# driver_board_v3_shift_regs.net
KiCad netlist of a schematic drawn in EAGLE
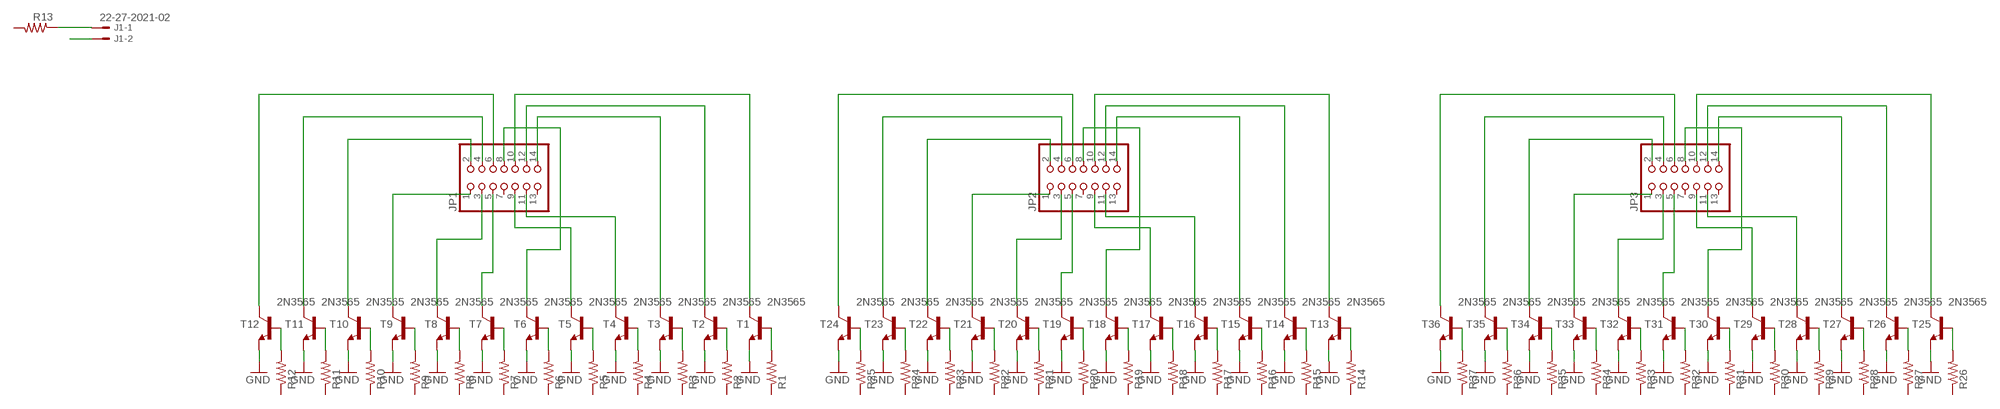
[diagram p0: schematic, sheet 1, part 1 of 2]
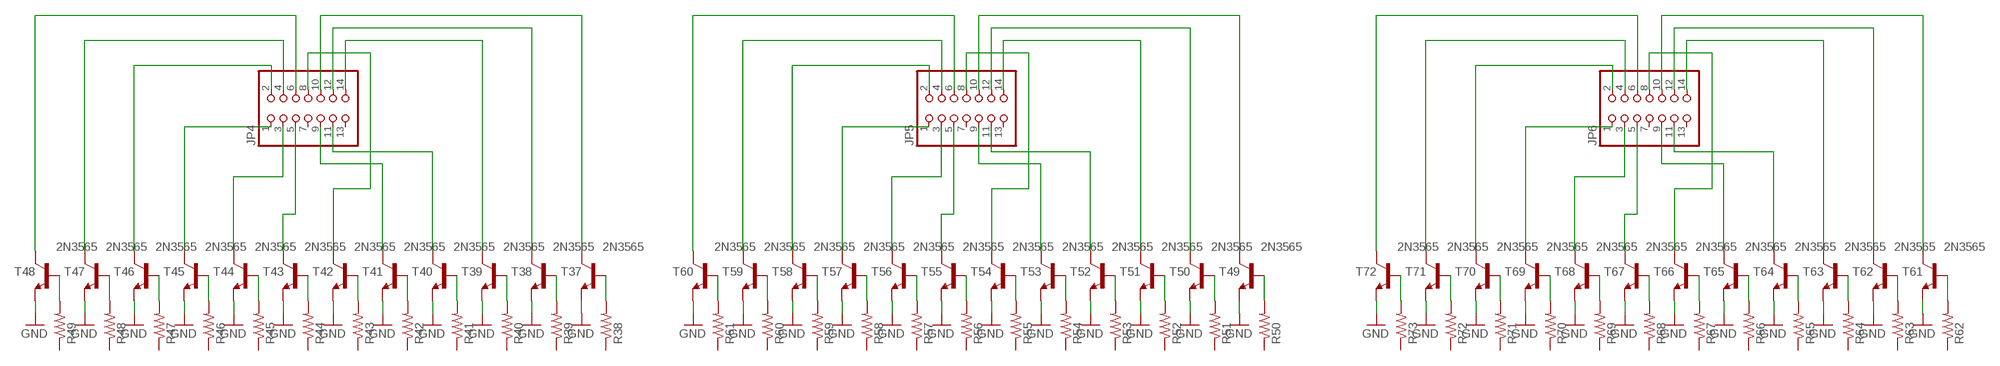
[diagram p1: schematic, sheet 1, part 2 of 2]

(export (version "E")
  (design (tool "Eeschema 10.0.6"))
  (components
    (comp (ref "J1")
      (value "22-27-2021-02")
      (footprint "eagle-import:6410-02")
      (libsource (lib "eagle-import") (part "22-?-0227-2021"))
    )
    (comp (ref "JP1")
      (value "PINHD-2X7")
      (footprint "eagle-import:2X07")
      (libsource (lib "eagle-import") (part "PINHD-2X7"))
    )
    (comp (ref "JP2")
      (value "PINHD-2X7")
      (footprint "eagle-import:2X07")
      (libsource (lib "eagle-import") (part "PINHD-2X7"))
    )
    (comp (ref "JP3")
      (value "PINHD-2X7")
      (footprint "eagle-import:2X07")
      (libsource (lib "eagle-import") (part "PINHD-2X7"))
    )
    (comp (ref "JP4")
      (value "PINHD-2X7")
      (footprint "eagle-import:2X07")
      (libsource (lib "eagle-import") (part "PINHD-2X7"))
    )
    (comp (ref "JP5")
      (value "PINHD-2X7")
      (footprint "eagle-import:2X07")
      (libsource (lib "eagle-import") (part "PINHD-2X7"))
    )
    (comp (ref "JP6")
      (value "PINHD-2X7")
      (footprint "eagle-import:2X07")
      (libsource (lib "eagle-import") (part "PINHD-2X7"))
    )
    (comp (ref "R1")
      (value "R-US_0204/7")
      (footprint "eagle-import:0204_7")
      (libsource (lib "eagle-import") (part "R-US_0204/7"))
    )
    (comp (ref "R2")
      (value "R-US_0204/7")
      (footprint "eagle-import:0204_7")
      (libsource (lib "eagle-import") (part "R-US_0204/7"))
    )
    (comp (ref "R3")
      (value "R-US_0204/7")
      (footprint "eagle-import:0204_7")
      (libsource (lib "eagle-import") (part "R-US_0204/7"))
    )
    (comp (ref "R4")
      (value "R-US_0204/7")
      (footprint "eagle-import:0204_7")
      (libsource (lib "eagle-import") (part "R-US_0204/7"))
    )
    (comp (ref "R5")
      (value "R-US_0204/7")
      (footprint "eagle-import:0204_7")
      (libsource (lib "eagle-import") (part "R-US_0204/7"))
    )
    (comp (ref "R6")
      (value "R-US_0204/7")
      (footprint "eagle-import:0204_7")
      (libsource (lib "eagle-import") (part "R-US_0204/7"))
    )
    (comp (ref "R7")
      (value "R-US_0204/7")
      (footprint "eagle-import:0204_7")
      (libsource (lib "eagle-import") (part "R-US_0204/7"))
    )
    (comp (ref "R8")
      (value "R-US_0204/7")
      (footprint "eagle-import:0204_7")
      (libsource (lib "eagle-import") (part "R-US_0204/7"))
    )
    (comp (ref "R9")
      (value "R-US_0204/7")
      (footprint "eagle-import:0204_7")
      (libsource (lib "eagle-import") (part "R-US_0204/7"))
    )
    (comp (ref "R10")
      (value "R-US_0204/7")
      (footprint "eagle-import:0204_7")
      (libsource (lib "eagle-import") (part "R-US_0204/7"))
    )
    (comp (ref "R11")
      (value "R-US_0204/7")
      (footprint "eagle-import:0204_7")
      (libsource (lib "eagle-import") (part "R-US_0204/7"))
    )
    (comp (ref "R12")
      (value "R-US_0204/7")
      (footprint "eagle-import:0204_7")
      (libsource (lib "eagle-import") (part "R-US_0204/7"))
    )
    (comp (ref "R13")
      (value "R-US_0204/7")
      (footprint "eagle-import:0204_7")
      (libsource (lib "eagle-import") (part "R-US_0204/7"))
    )
    (comp (ref "R14")
      (value "R-US_0204/7")
      (footprint "eagle-import:0204_7")
      (libsource (lib "eagle-import") (part "R-US_0204/7"))
    )
    (comp (ref "R15")
      (value "R-US_0204/7")
      (footprint "eagle-import:0204_7")
      (libsource (lib "eagle-import") (part "R-US_0204/7"))
    )
    (comp (ref "R16")
      (value "R-US_0204/7")
      (footprint "eagle-import:0204_7")
      (libsource (lib "eagle-import") (part "R-US_0204/7"))
    )
    (comp (ref "R17")
      (value "R-US_0204/7")
      (footprint "eagle-import:0204_7")
      (libsource (lib "eagle-import") (part "R-US_0204/7"))
    )
    (comp (ref "R18")
      (value "R-US_0204/7")
      (footprint "eagle-import:0204_7")
      (libsource (lib "eagle-import") (part "R-US_0204/7"))
    )
    (comp (ref "R19")
      (value "R-US_0204/7")
      (footprint "eagle-import:0204_7")
      (libsource (lib "eagle-import") (part "R-US_0204/7"))
    )
    (comp (ref "R20")
      (value "R-US_0204/7")
      (footprint "eagle-import:0204_7")
      (libsource (lib "eagle-import") (part "R-US_0204/7"))
    )
    (comp (ref "R21")
      (value "R-US_0204/7")
      (footprint "eagle-import:0204_7")
      (libsource (lib "eagle-import") (part "R-US_0204/7"))
    )
    (comp (ref "R22")
      (value "R-US_0204/7")
      (footprint "eagle-import:0204_7")
      (libsource (lib "eagle-import") (part "R-US_0204/7"))
    )
    (comp (ref "R23")
      (value "R-US_0204/7")
      (footprint "eagle-import:0204_7")
      (libsource (lib "eagle-import") (part "R-US_0204/7"))
    )
    (comp (ref "R24")
      (value "R-US_0204/7")
      (footprint "eagle-import:0204_7")
      (libsource (lib "eagle-import") (part "R-US_0204/7"))
    )
    (comp (ref "R25")
      (value "R-US_0204/7")
      (footprint "eagle-import:0204_7")
      (libsource (lib "eagle-import") (part "R-US_0204/7"))
    )
    (comp (ref "R26")
      (value "R-US_0204/7")
      (footprint "eagle-import:0204_7")
      (libsource (lib "eagle-import") (part "R-US_0204/7"))
    )
    (comp (ref "R27")
      (value "R-US_0204/7")
      (footprint "eagle-import:0204_7")
      (libsource (lib "eagle-import") (part "R-US_0204/7"))
    )
    (comp (ref "R28")
      (value "R-US_0204/7")
      (footprint "eagle-import:0204_7")
      (libsource (lib "eagle-import") (part "R-US_0204/7"))
    )
    (comp (ref "R29")
      (value "R-US_0204/7")
      (footprint "eagle-import:0204_7")
      (libsource (lib "eagle-import") (part "R-US_0204/7"))
    )
    (comp (ref "R30")
      (value "R-US_0204/7")
      (footprint "eagle-import:0204_7")
      (libsource (lib "eagle-import") (part "R-US_0204/7"))
    )
    (comp (ref "R31")
      (value "R-US_0204/7")
      (footprint "eagle-import:0204_7")
      (libsource (lib "eagle-import") (part "R-US_0204/7"))
    )
    (comp (ref "R32")
      (value "R-US_0204/7")
      (footprint "eagle-import:0204_7")
      (libsource (lib "eagle-import") (part "R-US_0204/7"))
    )
    (comp (ref "R33")
      (value "R-US_0204/7")
      (footprint "eagle-import:0204_7")
      (libsource (lib "eagle-import") (part "R-US_0204/7"))
    )
    (comp (ref "R34")
      (value "R-US_0204/7")
      (footprint "eagle-import:0204_7")
      (libsource (lib "eagle-import") (part "R-US_0204/7"))
    )
    (comp (ref "R35")
      (value "R-US_0204/7")
      (footprint "eagle-import:0204_7")
      (libsource (lib "eagle-import") (part "R-US_0204/7"))
    )
    (comp (ref "R36")
      (value "R-US_0204/7")
      (footprint "eagle-import:0204_7")
      (libsource (lib "eagle-import") (part "R-US_0204/7"))
    )
    (comp (ref "R37")
      (value "R-US_0204/7")
      (footprint "eagle-import:0204_7")
      (libsource (lib "eagle-import") (part "R-US_0204/7"))
    )
    (comp (ref "R38")
      (value "R-US_0204/7")
      (footprint "eagle-import:0204_7")
      (libsource (lib "eagle-import") (part "R-US_0204/7"))
    )
    (comp (ref "R39")
      (value "R-US_0204/7")
      (footprint "eagle-import:0204_7")
      (libsource (lib "eagle-import") (part "R-US_0204/7"))
    )
    (comp (ref "R40")
      (value "R-US_0204/7")
      (footprint "eagle-import:0204_7")
      (libsource (lib "eagle-import") (part "R-US_0204/7"))
    )
    (comp (ref "R41")
      (value "R-US_0204/7")
      (footprint "eagle-import:0204_7")
      (libsource (lib "eagle-import") (part "R-US_0204/7"))
    )
    (comp (ref "R42")
      (value "R-US_0204/7")
      (footprint "eagle-import:0204_7")
      (libsource (lib "eagle-import") (part "R-US_0204/7"))
    )
    (comp (ref "R43")
      (value "R-US_0204/7")
      (footprint "eagle-import:0204_7")
      (libsource (lib "eagle-import") (part "R-US_0204/7"))
    )
    (comp (ref "R44")
      (value "R-US_0204/7")
      (footprint "eagle-import:0204_7")
      (libsource (lib "eagle-import") (part "R-US_0204/7"))
    )
    (comp (ref "R45")
      (value "R-US_0204/7")
      (footprint "eagle-import:0204_7")
      (libsource (lib "eagle-import") (part "R-US_0204/7"))
    )
    (comp (ref "R46")
      (value "R-US_0204/7")
      (footprint "eagle-import:0204_7")
      (libsource (lib "eagle-import") (part "R-US_0204/7"))
    )
    (comp (ref "R47")
      (value "R-US_0204/7")
      (footprint "eagle-import:0204_7")
      (libsource (lib "eagle-import") (part "R-US_0204/7"))
    )
    (comp (ref "R48")
      (value "R-US_0204/7")
      (footprint "eagle-import:0204_7")
      (libsource (lib "eagle-import") (part "R-US_0204/7"))
    )
    (comp (ref "R49")
      (value "R-US_0204/7")
      (footprint "eagle-import:0204_7")
      (libsource (lib "eagle-import") (part "R-US_0204/7"))
    )
    (comp (ref "R50")
      (value "R-US_0204/7")
      (footprint "eagle-import:0204_7")
      (libsource (lib "eagle-import") (part "R-US_0204/7"))
    )
    (comp (ref "R51")
      (value "R-US_0204/7")
      (footprint "eagle-import:0204_7")
      (libsource (lib "eagle-import") (part "R-US_0204/7"))
    )
    (comp (ref "R52")
      (value "R-US_0204/7")
      (footprint "eagle-import:0204_7")
      (libsource (lib "eagle-import") (part "R-US_0204/7"))
    )
    (comp (ref "R53")
      (value "R-US_0204/7")
      (footprint "eagle-import:0204_7")
      (libsource (lib "eagle-import") (part "R-US_0204/7"))
    )
    (comp (ref "R54")
      (value "R-US_0204/7")
      (footprint "eagle-import:0204_7")
      (libsource (lib "eagle-import") (part "R-US_0204/7"))
    )
    (comp (ref "R55")
      (value "R-US_0204/7")
      (footprint "eagle-import:0204_7")
      (libsource (lib "eagle-import") (part "R-US_0204/7"))
    )
    (comp (ref "R56")
      (value "R-US_0204/7")
      (footprint "eagle-import:0204_7")
      (libsource (lib "eagle-import") (part "R-US_0204/7"))
    )
    (comp (ref "R57")
      (value "R-US_0204/7")
      (footprint "eagle-import:0204_7")
      (libsource (lib "eagle-import") (part "R-US_0204/7"))
    )
    (comp (ref "R58")
      (value "R-US_0204/7")
      (footprint "eagle-import:0204_7")
      (libsource (lib "eagle-import") (part "R-US_0204/7"))
    )
    (comp (ref "R59")
      (value "R-US_0204/7")
      (footprint "eagle-import:0204_7")
      (libsource (lib "eagle-import") (part "R-US_0204/7"))
    )
    (comp (ref "R60")
      (value "R-US_0204/7")
      (footprint "eagle-import:0204_7")
      (libsource (lib "eagle-import") (part "R-US_0204/7"))
    )
    (comp (ref "R61")
      (value "R-US_0204/7")
      (footprint "eagle-import:0204_7")
      (libsource (lib "eagle-import") (part "R-US_0204/7"))
    )
    (comp (ref "R62")
      (value "R-US_0204/7")
      (footprint "eagle-import:0204_7")
      (libsource (lib "eagle-import") (part "R-US_0204/7"))
    )
    (comp (ref "R63")
      (value "R-US_0204/7")
      (footprint "eagle-import:0204_7")
      (libsource (lib "eagle-import") (part "R-US_0204/7"))
    )
    (comp (ref "R64")
      (value "R-US_0204/7")
      (footprint "eagle-import:0204_7")
      (libsource (lib "eagle-import") (part "R-US_0204/7"))
    )
    (comp (ref "R65")
      (value "R-US_0204/7")
      (footprint "eagle-import:0204_7")
      (libsource (lib "eagle-import") (part "R-US_0204/7"))
    )
    (comp (ref "R66")
      (value "R-US_0204/7")
      (footprint "eagle-import:0204_7")
      (libsource (lib "eagle-import") (part "R-US_0204/7"))
    )
    (comp (ref "R67")
      (value "R-US_0204/7")
      (footprint "eagle-import:0204_7")
      (libsource (lib "eagle-import") (part "R-US_0204/7"))
    )
    (comp (ref "R68")
      (value "R-US_0204/7")
      (footprint "eagle-import:0204_7")
      (libsource (lib "eagle-import") (part "R-US_0204/7"))
    )
    (comp (ref "R69")
      (value "R-US_0204/7")
      (footprint "eagle-import:0204_7")
      (libsource (lib "eagle-import") (part "R-US_0204/7"))
    )
    (comp (ref "R70")
      (value "R-US_0204/7")
      (footprint "eagle-import:0204_7")
      (libsource (lib "eagle-import") (part "R-US_0204/7"))
    )
    (comp (ref "R71")
      (value "R-US_0204/7")
      (footprint "eagle-import:0204_7")
      (libsource (lib "eagle-import") (part "R-US_0204/7"))
    )
    (comp (ref "R72")
      (value "R-US_0204/7")
      (footprint "eagle-import:0204_7")
      (libsource (lib "eagle-import") (part "R-US_0204/7"))
    )
    (comp (ref "R73")
      (value "R-US_0204/7")
      (footprint "eagle-import:0204_7")
      (libsource (lib "eagle-import") (part "R-US_0204/7"))
    )
    (comp (ref "T1")
      (value "2N3565")
      (footprint "eagle-import:TO92")
      (libsource (lib "eagle-import") (part "2N3565"))
    )
    (comp (ref "T2")
      (value "2N3565")
      (footprint "eagle-import:TO92")
      (libsource (lib "eagle-import") (part "2N3565"))
    )
    (comp (ref "T3")
      (value "2N3565")
      (footprint "eagle-import:TO92")
      (libsource (lib "eagle-import") (part "2N3565"))
    )
    (comp (ref "T4")
      (value "2N3565")
      (footprint "eagle-import:TO92")
      (libsource (lib "eagle-import") (part "2N3565"))
    )
    (comp (ref "T5")
      (value "2N3565")
      (footprint "eagle-import:TO92")
      (libsource (lib "eagle-import") (part "2N3565"))
    )
    (comp (ref "T6")
      (value "2N3565")
      (footprint "eagle-import:TO92")
      (libsource (lib "eagle-import") (part "2N3565"))
    )
    (comp (ref "T7")
      (value "2N3565")
      (footprint "eagle-import:TO92")
      (libsource (lib "eagle-import") (part "2N3565"))
    )
    (comp (ref "T8")
      (value "2N3565")
      (footprint "eagle-import:TO92")
      (libsource (lib "eagle-import") (part "2N3565"))
    )
    (comp (ref "T9")
      (value "2N3565")
      (footprint "eagle-import:TO92")
      (libsource (lib "eagle-import") (part "2N3565"))
    )
    (comp (ref "T10")
      (value "2N3565")
      (footprint "eagle-import:TO92")
      (libsource (lib "eagle-import") (part "2N3565"))
    )
    (comp (ref "T11")
      (value "2N3565")
      (footprint "eagle-import:TO92")
      (libsource (lib "eagle-import") (part "2N3565"))
    )
    (comp (ref "T12")
      (value "2N3565")
      (footprint "eagle-import:TO92")
      (libsource (lib "eagle-import") (part "2N3565"))
    )
    (comp (ref "T13")
      (value "2N3565")
      (footprint "eagle-import:TO92")
      (libsource (lib "eagle-import") (part "2N3565"))
    )
    (comp (ref "T14")
      (value "2N3565")
      (footprint "eagle-import:TO92")
      (libsource (lib "eagle-import") (part "2N3565"))
    )
    (comp (ref "T15")
      (value "2N3565")
      (footprint "eagle-import:TO92")
      (libsource (lib "eagle-import") (part "2N3565"))
    )
    (comp (ref "T16")
      (value "2N3565")
      (footprint "eagle-import:TO92")
      (libsource (lib "eagle-import") (part "2N3565"))
    )
    (comp (ref "T17")
      (value "2N3565")
      (footprint "eagle-import:TO92")
      (libsource (lib "eagle-import") (part "2N3565"))
    )
    (comp (ref "T18")
      (value "2N3565")
      (footprint "eagle-import:TO92")
      (libsource (lib "eagle-import") (part "2N3565"))
    )
    (comp (ref "T19")
      (value "2N3565")
      (footprint "eagle-import:TO92")
      (libsource (lib "eagle-import") (part "2N3565"))
    )
    (comp (ref "T20")
      (value "2N3565")
      (footprint "eagle-import:TO92")
      (libsource (lib "eagle-import") (part "2N3565"))
    )
    (comp (ref "T21")
      (value "2N3565")
      (footprint "eagle-import:TO92")
      (libsource (lib "eagle-import") (part "2N3565"))
    )
    (comp (ref "T22")
      (value "2N3565")
      (footprint "eagle-import:TO92")
      (libsource (lib "eagle-import") (part "2N3565"))
    )
    (comp (ref "T23")
      (value "2N3565")
      (footprint "eagle-import:TO92")
      (libsource (lib "eagle-import") (part "2N3565"))
    )
    (comp (ref "T24")
      (value "2N3565")
      (footprint "eagle-import:TO92")
      (libsource (lib "eagle-import") (part "2N3565"))
    )
    (comp (ref "T25")
      (value "2N3565")
      (footprint "eagle-import:TO92")
      (libsource (lib "eagle-import") (part "2N3565"))
    )
    (comp (ref "T26")
      (value "2N3565")
      (footprint "eagle-import:TO92")
      (libsource (lib "eagle-import") (part "2N3565"))
    )
    (comp (ref "T27")
      (value "2N3565")
      (footprint "eagle-import:TO92")
      (libsource (lib "eagle-import") (part "2N3565"))
    )
    (comp (ref "T28")
      (value "2N3565")
      (footprint "eagle-import:TO92")
      (libsource (lib "eagle-import") (part "2N3565"))
    )
    (comp (ref "T29")
      (value "2N3565")
      (footprint "eagle-import:TO92")
      (libsource (lib "eagle-import") (part "2N3565"))
    )
    (comp (ref "T30")
      (value "2N3565")
      (footprint "eagle-import:TO92")
      (libsource (lib "eagle-import") (part "2N3565"))
    )
    (comp (ref "T31")
      (value "2N3565")
      (footprint "eagle-import:TO92")
      (libsource (lib "eagle-import") (part "2N3565"))
    )
    (comp (ref "T32")
      (value "2N3565")
      (footprint "eagle-import:TO92")
      (libsource (lib "eagle-import") (part "2N3565"))
    )
    (comp (ref "T33")
      (value "2N3565")
      (footprint "eagle-import:TO92")
      (libsource (lib "eagle-import") (part "2N3565"))
    )
    (comp (ref "T34")
      (value "2N3565")
      (footprint "eagle-import:TO92")
      (libsource (lib "eagle-import") (part "2N3565"))
    )
    (comp (ref "T35")
      (value "2N3565")
      (footprint "eagle-import:TO92")
      (libsource (lib "eagle-import") (part "2N3565"))
    )
    (comp (ref "T36")
      (value "2N3565")
      (footprint "eagle-import:TO92")
      (libsource (lib "eagle-import") (part "2N3565"))
    )
    (comp (ref "T37")
      (value "2N3565")
      (footprint "eagle-import:TO92")
      (libsource (lib "eagle-import") (part "2N3565"))
    )
    (comp (ref "T38")
      (value "2N3565")
      (footprint "eagle-import:TO92")
      (libsource (lib "eagle-import") (part "2N3565"))
    )
    (comp (ref "T39")
      (value "2N3565")
      (footprint "eagle-import:TO92")
      (libsource (lib "eagle-import") (part "2N3565"))
    )
    (comp (ref "T40")
      (value "2N3565")
      (footprint "eagle-import:TO92")
      (libsource (lib "eagle-import") (part "2N3565"))
    )
    (comp (ref "T41")
      (value "2N3565")
      (footprint "eagle-import:TO92")
      (libsource (lib "eagle-import") (part "2N3565"))
    )
    (comp (ref "T42")
      (value "2N3565")
      (footprint "eagle-import:TO92")
      (libsource (lib "eagle-import") (part "2N3565"))
    )
    (comp (ref "T43")
      (value "2N3565")
      (footprint "eagle-import:TO92")
      (libsource (lib "eagle-import") (part "2N3565"))
    )
    (comp (ref "T44")
      (value "2N3565")
      (footprint "eagle-import:TO92")
      (libsource (lib "eagle-import") (part "2N3565"))
    )
    (comp (ref "T45")
      (value "2N3565")
      (footprint "eagle-import:TO92")
      (libsource (lib "eagle-import") (part "2N3565"))
    )
    (comp (ref "T46")
      (value "2N3565")
      (footprint "eagle-import:TO92")
      (libsource (lib "eagle-import") (part "2N3565"))
    )
    (comp (ref "T47")
      (value "2N3565")
      (footprint "eagle-import:TO92")
      (libsource (lib "eagle-import") (part "2N3565"))
    )
    (comp (ref "T48")
      (value "2N3565")
      (footprint "eagle-import:TO92")
      (libsource (lib "eagle-import") (part "2N3565"))
    )
    (comp (ref "T49")
      (value "2N3565")
      (footprint "eagle-import:TO92")
      (libsource (lib "eagle-import") (part "2N3565"))
    )
    (comp (ref "T50")
      (value "2N3565")
      (footprint "eagle-import:TO92")
      (libsource (lib "eagle-import") (part "2N3565"))
    )
    (comp (ref "T51")
      (value "2N3565")
      (footprint "eagle-import:TO92")
      (libsource (lib "eagle-import") (part "2N3565"))
    )
    (comp (ref "T52")
      (value "2N3565")
      (footprint "eagle-import:TO92")
      (libsource (lib "eagle-import") (part "2N3565"))
    )
    (comp (ref "T53")
      (value "2N3565")
      (footprint "eagle-import:TO92")
      (libsource (lib "eagle-import") (part "2N3565"))
    )
    (comp (ref "T54")
      (value "2N3565")
      (footprint "eagle-import:TO92")
      (libsource (lib "eagle-import") (part "2N3565"))
    )
    (comp (ref "T55")
      (value "2N3565")
      (footprint "eagle-import:TO92")
      (libsource (lib "eagle-import") (part "2N3565"))
    )
    (comp (ref "T56")
      (value "2N3565")
      (footprint "eagle-import:TO92")
      (libsource (lib "eagle-import") (part "2N3565"))
    )
    (comp (ref "T57")
      (value "2N3565")
      (footprint "eagle-import:TO92")
      (libsource (lib "eagle-import") (part "2N3565"))
    )
    (comp (ref "T58")
      (value "2N3565")
      (footprint "eagle-import:TO92")
      (libsource (lib "eagle-import") (part "2N3565"))
    )
    (comp (ref "T59")
      (value "2N3565")
      (footprint "eagle-import:TO92")
      (libsource (lib "eagle-import") (part "2N3565"))
    )
    (comp (ref "T60")
      (value "2N3565")
      (footprint "eagle-import:TO92")
      (libsource (lib "eagle-import") (part "2N3565"))
    )
    (comp (ref "T61")
      (value "2N3565")
      (footprint "eagle-import:TO92")
      (libsource (lib "eagle-import") (part "2N3565"))
    )
    (comp (ref "T62")
      (value "2N3565")
      (footprint "eagle-import:TO92")
      (libsource (lib "eagle-import") (part "2N3565"))
    )
    (comp (ref "T63")
      (value "2N3565")
      (footprint "eagle-import:TO92")
      (libsource (lib "eagle-import") (part "2N3565"))
    )
    (comp (ref "T64")
      (value "2N3565")
      (footprint "eagle-import:TO92")
      (libsource (lib "eagle-import") (part "2N3565"))
    )
    (comp (ref "T65")
      (value "2N3565")
      (footprint "eagle-import:TO92")
      (libsource (lib "eagle-import") (part "2N3565"))
    )
    (comp (ref "T66")
      (value "2N3565")
      (footprint "eagle-import:TO92")
      (libsource (lib "eagle-import") (part "2N3565"))
    )
    (comp (ref "T67")
      (value "2N3565")
      (footprint "eagle-import:TO92")
      (libsource (lib "eagle-import") (part "2N3565"))
    )
    (comp (ref "T68")
      (value "2N3565")
      (footprint "eagle-import:TO92")
      (libsource (lib "eagle-import") (part "2N3565"))
    )
    (comp (ref "T69")
      (value "2N3565")
      (footprint "eagle-import:TO92")
      (libsource (lib "eagle-import") (part "2N3565"))
    )
    (comp (ref "T70")
      (value "2N3565")
      (footprint "eagle-import:TO92")
      (libsource (lib "eagle-import") (part "2N3565"))
    )
    (comp (ref "T71")
      (value "2N3565")
      (footprint "eagle-import:TO92")
      (libsource (lib "eagle-import") (part "2N3565"))
    )
    (comp (ref "T72")
      (value "2N3565")
      (footprint "eagle-import:TO92")
      (libsource (lib "eagle-import") (part "2N3565"))
    )
  )
  (nets
    (net (code "1") (name "GND") (class "Default")
      (node (ref "T1") (pin "3") (pinfunction "E_3") (pintype "passive"))
      (node (ref "T10") (pin "3") (pinfunction "E_3") (pintype "passive"))
      (node (ref "T11") (pin "3") (pinfunction "E_3") (pintype "passive"))
      (node (ref "T12") (pin "3") (pinfunction "E_3") (pintype "passive"))
      (node (ref "T13") (pin "3") (pinfunction "E_3") (pintype "passive"))
      (node (ref "T14") (pin "3") (pinfunction "E_3") (pintype "passive"))
      (node (ref "T15") (pin "3") (pinfunction "E_3") (pintype "passive"))
      (node (ref "T16") (pin "3") (pinfunction "E_3") (pintype "passive"))
      (node (ref "T17") (pin "3") (pinfunction "E_3") (pintype "passive"))
      (node (ref "T18") (pin "3") (pinfunction "E_3") (pintype "passive"))
      (node (ref "T19") (pin "3") (pinfunction "E_3") (pintype "passive"))
      (node (ref "T2") (pin "3") (pinfunction "E_3") (pintype "passive"))
      (node (ref "T20") (pin "3") (pinfunction "E_3") (pintype "passive"))
      (node (ref "T21") (pin "3") (pinfunction "E_3") (pintype "passive"))
      (node (ref "T22") (pin "3") (pinfunction "E_3") (pintype "passive"))
      (node (ref "T23") (pin "3") (pinfunction "E_3") (pintype "passive"))
      (node (ref "T24") (pin "3") (pinfunction "E_3") (pintype "passive"))
      (node (ref "T25") (pin "3") (pinfunction "E_3") (pintype "passive"))
      (node (ref "T26") (pin "3") (pinfunction "E_3") (pintype "passive"))
      (node (ref "T27") (pin "3") (pinfunction "E_3") (pintype "passive"))
      (node (ref "T28") (pin "3") (pinfunction "E_3") (pintype "passive"))
      (node (ref "T29") (pin "3") (pinfunction "E_3") (pintype "passive"))
      (node (ref "T3") (pin "3") (pinfunction "E_3") (pintype "passive"))
      (node (ref "T30") (pin "3") (pinfunction "E_3") (pintype "passive"))
      (node (ref "T31") (pin "3") (pinfunction "E_3") (pintype "passive"))
      (node (ref "T32") (pin "3") (pinfunction "E_3") (pintype "passive"))
      (node (ref "T33") (pin "3") (pinfunction "E_3") (pintype "passive"))
      (node (ref "T34") (pin "3") (pinfunction "E_3") (pintype "passive"))
      (node (ref "T35") (pin "3") (pinfunction "E_3") (pintype "passive"))
      (node (ref "T36") (pin "3") (pinfunction "E_3") (pintype "passive"))
      (node (ref "T37") (pin "3") (pinfunction "E_3") (pintype "passive"))
      (node (ref "T38") (pin "3") (pinfunction "E_3") (pintype "passive"))
      (node (ref "T39") (pin "3") (pinfunction "E_3") (pintype "passive"))
      (node (ref "T4") (pin "3") (pinfunction "E_3") (pintype "passive"))
      (node (ref "T40") (pin "3") (pinfunction "E_3") (pintype "passive"))
      (node (ref "T41") (pin "3") (pinfunction "E_3") (pintype "passive"))
      (node (ref "T42") (pin "3") (pinfunction "E_3") (pintype "passive"))
      (node (ref "T43") (pin "3") (pinfunction "E_3") (pintype "passive"))
      (node (ref "T44") (pin "3") (pinfunction "E_3") (pintype "passive"))
      (node (ref "T45") (pin "3") (pinfunction "E_3") (pintype "passive"))
      (node (ref "T46") (pin "3") (pinfunction "E_3") (pintype "passive"))
      (node (ref "T47") (pin "3") (pinfunction "E_3") (pintype "passive"))
      (node (ref "T48") (pin "3") (pinfunction "E_3") (pintype "passive"))
      (node (ref "T49") (pin "3") (pinfunction "E_3") (pintype "passive"))
      (node (ref "T5") (pin "3") (pinfunction "E_3") (pintype "passive"))
      (node (ref "T50") (pin "3") (pinfunction "E_3") (pintype "passive"))
      (node (ref "T51") (pin "3") (pinfunction "E_3") (pintype "passive"))
      (node (ref "T52") (pin "3") (pinfunction "E_3") (pintype "passive"))
      (node (ref "T53") (pin "3") (pinfunction "E_3") (pintype "passive"))
      (node (ref "T54") (pin "3") (pinfunction "E_3") (pintype "passive"))
      (node (ref "T55") (pin "3") (pinfunction "E_3") (pintype "passive"))
      (node (ref "T56") (pin "3") (pinfunction "E_3") (pintype "passive"))
      (node (ref "T57") (pin "3") (pinfunction "E_3") (pintype "passive"))
      (node (ref "T58") (pin "3") (pinfunction "E_3") (pintype "passive"))
      (node (ref "T59") (pin "3") (pinfunction "E_3") (pintype "passive"))
      (node (ref "T6") (pin "3") (pinfunction "E_3") (pintype "passive"))
      (node (ref "T60") (pin "3") (pinfunction "E_3") (pintype "passive"))
      (node (ref "T61") (pin "3") (pinfunction "E_3") (pintype "passive"))
      (node (ref "T62") (pin "3") (pinfunction "E_3") (pintype "passive"))
      (node (ref "T63") (pin "3") (pinfunction "E_3") (pintype "passive"))
      (node (ref "T64") (pin "3") (pinfunction "E_3") (pintype "passive"))
      (node (ref "T65") (pin "3") (pinfunction "E_3") (pintype "passive"))
      (node (ref "T66") (pin "3") (pinfunction "E_3") (pintype "passive"))
      (node (ref "T67") (pin "3") (pinfunction "E_3") (pintype "passive"))
      (node (ref "T68") (pin "3") (pinfunction "E_3") (pintype "passive"))
      (node (ref "T69") (pin "3") (pinfunction "E_3") (pintype "passive"))
      (node (ref "T7") (pin "3") (pinfunction "E_3") (pintype "passive"))
      (node (ref "T70") (pin "3") (pinfunction "E_3") (pintype "passive"))
      (node (ref "T71") (pin "3") (pinfunction "E_3") (pintype "passive"))
      (node (ref "T72") (pin "3") (pinfunction "E_3") (pintype "passive"))
      (node (ref "T8") (pin "3") (pinfunction "E_3") (pintype "passive"))
      (node (ref "T9") (pin "3") (pinfunction "E_3") (pintype "passive"))
    )
    (net (code "2") (name "Net-(J1A-S)") (class "Default")
      (node (ref "J1") (pin "1") (pinfunction "S_1") (pintype "passive"))
      (node (ref "R13") (pin "1") (pinfunction "1_1") (pintype "passive"))
    )
    (net (code "3") (name "Net-(T1-B)") (class "Default")
      (node (ref "R1") (pin "2") (pinfunction "2_2") (pintype "passive"))
      (node (ref "T1") (pin "2") (pinfunction "B_2") (pintype "passive"))
    )
    (net (code "4") (name "Net-(T1-C)") (class "Default")
      (node (ref "JP1") (pin "10") (pinfunction "10_10") (pintype "passive"))
      (node (ref "T1") (pin "1") (pinfunction "C_1") (pintype "passive"))
    )
    (net (code "5") (name "Net-(T2-B)") (class "Default")
      (node (ref "R2") (pin "2") (pinfunction "2_2") (pintype "passive"))
      (node (ref "T2") (pin "2") (pinfunction "B_2") (pintype "passive"))
    )
    (net (code "6") (name "Net-(T2-C)") (class "Default")
      (node (ref "JP1") (pin "12") (pinfunction "12_12") (pintype "passive"))
      (node (ref "T2") (pin "1") (pinfunction "C_1") (pintype "passive"))
    )
    (net (code "7") (name "Net-(T3-B)") (class "Default")
      (node (ref "R3") (pin "2") (pinfunction "2_2") (pintype "passive"))
      (node (ref "T3") (pin "2") (pinfunction "B_2") (pintype "passive"))
    )
    (net (code "8") (name "Net-(T3-C)") (class "Default")
      (node (ref "JP1") (pin "14") (pinfunction "14_14") (pintype "passive"))
      (node (ref "T3") (pin "1") (pinfunction "C_1") (pintype "passive"))
    )
    (net (code "9") (name "Net-(T4-B)") (class "Default")
      (node (ref "R4") (pin "2") (pinfunction "2_2") (pintype "passive"))
      (node (ref "T4") (pin "2") (pinfunction "B_2") (pintype "passive"))
    )
    (net (code "10") (name "Net-(T4-C)") (class "Default")
      (node (ref "JP1") (pin "11") (pinfunction "11_11") (pintype "passive"))
      (node (ref "T4") (pin "1") (pinfunction "C_1") (pintype "passive"))
    )
    (net (code "11") (name "Net-(T5-B)") (class "Default")
      (node (ref "R5") (pin "2") (pinfunction "2_2") (pintype "passive"))
      (node (ref "T5") (pin "2") (pinfunction "B_2") (pintype "passive"))
    )
    (net (code "12") (name "Net-(T5-C)") (class "Default")
      (node (ref "JP1") (pin "9") (pinfunction "9_9") (pintype "passive"))
      (node (ref "T5") (pin "1") (pinfunction "C_1") (pintype "passive"))
    )
    (net (code "13") (name "Net-(T6-B)") (class "Default")
      (node (ref "R6") (pin "2") (pinfunction "2_2") (pintype "passive"))
      (node (ref "T6") (pin "2") (pinfunction "B_2") (pintype "passive"))
    )
    (net (code "14") (name "Net-(T6-C)") (class "Default")
      (node (ref "JP1") (pin "8") (pinfunction "8_8") (pintype "passive"))
      (node (ref "T6") (pin "1") (pinfunction "C_1") (pintype "passive"))
    )
    (net (code "15") (name "Net-(T7-B)") (class "Default")
      (node (ref "R7") (pin "2") (pinfunction "2_2") (pintype "passive"))
      (node (ref "T7") (pin "2") (pinfunction "B_2") (pintype "passive"))
    )
    (net (code "16") (name "Net-(T7-C)") (class "Default")
      (node (ref "JP1") (pin "5") (pinfunction "5_5") (pintype "passive"))
      (node (ref "T7") (pin "1") (pinfunction "C_1") (pintype "passive"))
    )
    (net (code "17") (name "Net-(T8-B)") (class "Default")
      (node (ref "R8") (pin "2") (pinfunction "2_2") (pintype "passive"))
      (node (ref "T8") (pin "2") (pinfunction "B_2") (pintype "passive"))
    )
    (net (code "18") (name "Net-(T8-C)") (class "Default")
      (node (ref "JP1") (pin "3") (pinfunction "3_3") (pintype "passive"))
      (node (ref "T8") (pin "1") (pinfunction "C_1") (pintype "passive"))
    )
    (net (code "19") (name "Net-(T9-B)") (class "Default")
      (node (ref "R9") (pin "2") (pinfunction "2_2") (pintype "passive"))
      (node (ref "T9") (pin "2") (pinfunction "B_2") (pintype "passive"))
    )
    (net (code "20") (name "Net-(T9-C)") (class "Default")
      (node (ref "JP1") (pin "1") (pinfunction "1_1") (pintype "passive"))
      (node (ref "T9") (pin "1") (pinfunction "C_1") (pintype "passive"))
    )
    (net (code "21") (name "Net-(T10-B)") (class "Default")
      (node (ref "R10") (pin "2") (pinfunction "2_2") (pintype "passive"))
      (node (ref "T10") (pin "2") (pinfunction "B_2") (pintype "passive"))
    )
    (net (code "22") (name "Net-(T10-C)") (class "Default")
      (node (ref "JP1") (pin "2") (pinfunction "2_2") (pintype "passive"))
      (node (ref "T10") (pin "1") (pinfunction "C_1") (pintype "passive"))
    )
    (net (code "23") (name "Net-(T11-B)") (class "Default")
      (node (ref "R11") (pin "2") (pinfunction "2_2") (pintype "passive"))
      (node (ref "T11") (pin "2") (pinfunction "B_2") (pintype "passive"))
    )
    (net (code "24") (name "Net-(T11-C)") (class "Default")
      (node (ref "JP1") (pin "4") (pinfunction "4_4") (pintype "passive"))
      (node (ref "T11") (pin "1") (pinfunction "C_1") (pintype "passive"))
    )
    (net (code "25") (name "Net-(T12-B)") (class "Default")
      (node (ref "R12") (pin "2") (pinfunction "2_2") (pintype "passive"))
      (node (ref "T12") (pin "2") (pinfunction "B_2") (pintype "passive"))
    )
    (net (code "26") (name "Net-(T12-C)") (class "Default")
      (node (ref "JP1") (pin "6") (pinfunction "6_6") (pintype "passive"))
      (node (ref "T12") (pin "1") (pinfunction "C_1") (pintype "passive"))
    )
    (net (code "27") (name "Net-(T13-B)") (class "Default")
      (node (ref "R14") (pin "2") (pinfunction "2_2") (pintype "passive"))
      (node (ref "T13") (pin "2") (pinfunction "B_2") (pintype "passive"))
    )
    (net (code "28") (name "Net-(T13-C)") (class "Default")
      (node (ref "JP2") (pin "10") (pinfunction "10_10") (pintype "passive"))
      (node (ref "T13") (pin "1") (pinfunction "C_1") (pintype "passive"))
    )
    (net (code "29") (name "Net-(T14-B)") (class "Default")
      (node (ref "R15") (pin "2") (pinfunction "2_2") (pintype "passive"))
      (node (ref "T14") (pin "2") (pinfunction "B_2") (pintype "passive"))
    )
    (net (code "30") (name "Net-(T14-C)") (class "Default")
      (node (ref "JP2") (pin "12") (pinfunction "12_12") (pintype "passive"))
      (node (ref "T14") (pin "1") (pinfunction "C_1") (pintype "passive"))
    )
    (net (code "31") (name "Net-(T15-B)") (class "Default")
      (node (ref "R16") (pin "2") (pinfunction "2_2") (pintype "passive"))
      (node (ref "T15") (pin "2") (pinfunction "B_2") (pintype "passive"))
    )
    (net (code "32") (name "Net-(T15-C)") (class "Default")
      (node (ref "JP2") (pin "14") (pinfunction "14_14") (pintype "passive"))
      (node (ref "T15") (pin "1") (pinfunction "C_1") (pintype "passive"))
    )
    (net (code "33") (name "Net-(T16-B)") (class "Default")
      (node (ref "R17") (pin "2") (pinfunction "2_2") (pintype "passive"))
      (node (ref "T16") (pin "2") (pinfunction "B_2") (pintype "passive"))
    )
    (net (code "34") (name "Net-(T16-C)") (class "Default")
      (node (ref "JP2") (pin "11") (pinfunction "11_11") (pintype "passive"))
      (node (ref "T16") (pin "1") (pinfunction "C_1") (pintype "passive"))
    )
    (net (code "35") (name "Net-(T17-B)") (class "Default")
      (node (ref "R18") (pin "2") (pinfunction "2_2") (pintype "passive"))
      (node (ref "T17") (pin "2") (pinfunction "B_2") (pintype "passive"))
    )
    (net (code "36") (name "Net-(T17-C)") (class "Default")
      (node (ref "JP2") (pin "9") (pinfunction "9_9") (pintype "passive"))
      (node (ref "T17") (pin "1") (pinfunction "C_1") (pintype "passive"))
    )
    (net (code "37") (name "Net-(T18-B)") (class "Default")
      (node (ref "R19") (pin "2") (pinfunction "2_2") (pintype "passive"))
      (node (ref "T18") (pin "2") (pinfunction "B_2") (pintype "passive"))
    )
    (net (code "38") (name "Net-(T18-C)") (class "Default")
      (node (ref "JP2") (pin "8") (pinfunction "8_8") (pintype "passive"))
      (node (ref "T18") (pin "1") (pinfunction "C_1") (pintype "passive"))
    )
    (net (code "39") (name "Net-(T19-B)") (class "Default")
      (node (ref "R20") (pin "2") (pinfunction "2_2") (pintype "passive"))
      (node (ref "T19") (pin "2") (pinfunction "B_2") (pintype "passive"))
    )
    (net (code "40") (name "Net-(T19-C)") (class "Default")
      (node (ref "JP2") (pin "5") (pinfunction "5_5") (pintype "passive"))
      (node (ref "T19") (pin "1") (pinfunction "C_1") (pintype "passive"))
    )
    (net (code "41") (name "Net-(T20-B)") (class "Default")
      (node (ref "R21") (pin "2") (pinfunction "2_2") (pintype "passive"))
      (node (ref "T20") (pin "2") (pinfunction "B_2") (pintype "passive"))
    )
    (net (code "42") (name "Net-(T20-C)") (class "Default")
      (node (ref "JP2") (pin "3") (pinfunction "3_3") (pintype "passive"))
      (node (ref "T20") (pin "1") (pinfunction "C_1") (pintype "passive"))
    )
    (net (code "43") (name "Net-(T21-B)") (class "Default")
      (node (ref "R22") (pin "2") (pinfunction "2_2") (pintype "passive"))
      (node (ref "T21") (pin "2") (pinfunction "B_2") (pintype "passive"))
    )
    (net (code "44") (name "Net-(T21-C)") (class "Default")
      (node (ref "JP2") (pin "1") (pinfunction "1_1") (pintype "passive"))
      (node (ref "T21") (pin "1") (pinfunction "C_1") (pintype "passive"))
    )
    (net (code "45") (name "Net-(T22-B)") (class "Default")
      (node (ref "R23") (pin "2") (pinfunction "2_2") (pintype "passive"))
      (node (ref "T22") (pin "2") (pinfunction "B_2") (pintype "passive"))
    )
    (net (code "46") (name "Net-(T22-C)") (class "Default")
      (node (ref "JP2") (pin "2") (pinfunction "2_2") (pintype "passive"))
      (node (ref "T22") (pin "1") (pinfunction "C_1") (pintype "passive"))
    )
    (net (code "47") (name "Net-(T23-B)") (class "Default")
      (node (ref "R24") (pin "2") (pinfunction "2_2") (pintype "passive"))
      (node (ref "T23") (pin "2") (pinfunction "B_2") (pintype "passive"))
    )
    (net (code "48") (name "Net-(T23-C)") (class "Default")
      (node (ref "JP2") (pin "4") (pinfunction "4_4") (pintype "passive"))
      (node (ref "T23") (pin "1") (pinfunction "C_1") (pintype "passive"))
    )
    (net (code "49") (name "Net-(T24-B)") (class "Default")
      (node (ref "R25") (pin "2") (pinfunction "2_2") (pintype "passive"))
      (node (ref "T24") (pin "2") (pinfunction "B_2") (pintype "passive"))
    )
    (net (code "50") (name "Net-(T24-C)") (class "Default")
      (node (ref "JP2") (pin "6") (pinfunction "6_6") (pintype "passive"))
      (node (ref "T24") (pin "1") (pinfunction "C_1") (pintype "passive"))
    )
    (net (code "51") (name "Net-(T25-B)") (class "Default")
      (node (ref "R26") (pin "2") (pinfunction "2_2") (pintype "passive"))
      (node (ref "T25") (pin "2") (pinfunction "B_2") (pintype "passive"))
    )
    (net (code "52") (name "Net-(T25-C)") (class "Default")
      (node (ref "JP3") (pin "10") (pinfunction "10_10") (pintype "passive"))
      (node (ref "T25") (pin "1") (pinfunction "C_1") (pintype "passive"))
    )
    (net (code "53") (name "Net-(T26-B)") (class "Default")
      (node (ref "R27") (pin "2") (pinfunction "2_2") (pintype "passive"))
      (node (ref "T26") (pin "2") (pinfunction "B_2") (pintype "passive"))
    )
    (net (code "54") (name "Net-(T26-C)") (class "Default")
      (node (ref "JP3") (pin "12") (pinfunction "12_12") (pintype "passive"))
      (node (ref "T26") (pin "1") (pinfunction "C_1") (pintype "passive"))
    )
    (net (code "55") (name "Net-(T27-B)") (class "Default")
      (node (ref "R28") (pin "2") (pinfunction "2_2") (pintype "passive"))
      (node (ref "T27") (pin "2") (pinfunction "B_2") (pintype "passive"))
    )
    (net (code "56") (name "Net-(T27-C)") (class "Default")
      (node (ref "JP3") (pin "14") (pinfunction "14_14") (pintype "passive"))
      (node (ref "T27") (pin "1") (pinfunction "C_1") (pintype "passive"))
    )
    (net (code "57") (name "Net-(T28-B)") (class "Default")
      (node (ref "R29") (pin "2") (pinfunction "2_2") (pintype "passive"))
      (node (ref "T28") (pin "2") (pinfunction "B_2") (pintype "passive"))
    )
    (net (code "58") (name "Net-(T28-C)") (class "Default")
      (node (ref "JP3") (pin "11") (pinfunction "11_11") (pintype "passive"))
      (node (ref "T28") (pin "1") (pinfunction "C_1") (pintype "passive"))
    )
    (net (code "59") (name "Net-(T29-B)") (class "Default")
      (node (ref "R30") (pin "2") (pinfunction "2_2") (pintype "passive"))
      (node (ref "T29") (pin "2") (pinfunction "B_2") (pintype "passive"))
    )
    (net (code "60") (name "Net-(T29-C)") (class "Default")
      (node (ref "JP3") (pin "9") (pinfunction "9_9") (pintype "passive"))
      (node (ref "T29") (pin "1") (pinfunction "C_1") (pintype "passive"))
    )
    (net (code "61") (name "Net-(T30-B)") (class "Default")
      (node (ref "R31") (pin "2") (pinfunction "2_2") (pintype "passive"))
      (node (ref "T30") (pin "2") (pinfunction "B_2") (pintype "passive"))
    )
    (net (code "62") (name "Net-(T30-C)") (class "Default")
      (node (ref "JP3") (pin "8") (pinfunction "8_8") (pintype "passive"))
      (node (ref "T30") (pin "1") (pinfunction "C_1") (pintype "passive"))
    )
    (net (code "63") (name "Net-(T31-B)") (class "Default")
      (node (ref "R32") (pin "2") (pinfunction "2_2") (pintype "passive"))
      (node (ref "T31") (pin "2") (pinfunction "B_2") (pintype "passive"))
    )
    (net (code "64") (name "Net-(T31-C)") (class "Default")
      (node (ref "JP3") (pin "5") (pinfunction "5_5") (pintype "passive"))
      (node (ref "T31") (pin "1") (pinfunction "C_1") (pintype "passive"))
    )
    (net (code "65") (name "Net-(T32-B)") (class "Default")
      (node (ref "R33") (pin "2") (pinfunction "2_2") (pintype "passive"))
      (node (ref "T32") (pin "2") (pinfunction "B_2") (pintype "passive"))
    )
    (net (code "66") (name "Net-(T32-C)") (class "Default")
      (node (ref "JP3") (pin "3") (pinfunction "3_3") (pintype "passive"))
      (node (ref "T32") (pin "1") (pinfunction "C_1") (pintype "passive"))
    )
    (net (code "67") (name "Net-(T33-B)") (class "Default")
      (node (ref "R34") (pin "2") (pinfunction "2_2") (pintype "passive"))
      (node (ref "T33") (pin "2") (pinfunction "B_2") (pintype "passive"))
    )
    (net (code "68") (name "Net-(T33-C)") (class "Default")
      (node (ref "JP3") (pin "1") (pinfunction "1_1") (pintype "passive"))
      (node (ref "T33") (pin "1") (pinfunction "C_1") (pintype "passive"))
    )
    (net (code "69") (name "Net-(T34-B)") (class "Default")
      (node (ref "R35") (pin "2") (pinfunction "2_2") (pintype "passive"))
      (node (ref "T34") (pin "2") (pinfunction "B_2") (pintype "passive"))
    )
    (net (code "70") (name "Net-(T34-C)") (class "Default")
      (node (ref "JP3") (pin "2") (pinfunction "2_2") (pintype "passive"))
      (node (ref "T34") (pin "1") (pinfunction "C_1") (pintype "passive"))
    )
    (net (code "71") (name "Net-(T35-B)") (class "Default")
      (node (ref "R36") (pin "2") (pinfunction "2_2") (pintype "passive"))
      (node (ref "T35") (pin "2") (pinfunction "B_2") (pintype "passive"))
    )
    (net (code "72") (name "Net-(T35-C)") (class "Default")
      (node (ref "JP3") (pin "4") (pinfunction "4_4") (pintype "passive"))
      (node (ref "T35") (pin "1") (pinfunction "C_1") (pintype "passive"))
    )
    (net (code "73") (name "Net-(T36-B)") (class "Default")
      (node (ref "R37") (pin "2") (pinfunction "2_2") (pintype "passive"))
      (node (ref "T36") (pin "2") (pinfunction "B_2") (pintype "passive"))
    )
    (net (code "74") (name "Net-(T36-C)") (class "Default")
      (node (ref "JP3") (pin "6") (pinfunction "6_6") (pintype "passive"))
      (node (ref "T36") (pin "1") (pinfunction "C_1") (pintype "passive"))
    )
    (net (code "75") (name "Net-(T37-B)") (class "Default")
      (node (ref "R38") (pin "2") (pinfunction "2_2") (pintype "passive"))
      (node (ref "T37") (pin "2") (pinfunction "B_2") (pintype "passive"))
    )
    (net (code "76") (name "Net-(T37-C)") (class "Default")
      (node (ref "JP4") (pin "10") (pinfunction "10_10") (pintype "passive"))
      (node (ref "T37") (pin "1") (pinfunction "C_1") (pintype "passive"))
    )
    (net (code "77") (name "Net-(T38-B)") (class "Default")
      (node (ref "R39") (pin "2") (pinfunction "2_2") (pintype "passive"))
      (node (ref "T38") (pin "2") (pinfunction "B_2") (pintype "passive"))
    )
    (net (code "78") (name "Net-(T38-C)") (class "Default")
      (node (ref "JP4") (pin "12") (pinfunction "12_12") (pintype "passive"))
      (node (ref "T38") (pin "1") (pinfunction "C_1") (pintype "passive"))
    )
    (net (code "79") (name "Net-(T39-B)") (class "Default")
      (node (ref "R40") (pin "2") (pinfunction "2_2") (pintype "passive"))
      (node (ref "T39") (pin "2") (pinfunction "B_2") (pintype "passive"))
    )
    (net (code "80") (name "Net-(T39-C)") (class "Default")
      (node (ref "JP4") (pin "14") (pinfunction "14_14") (pintype "passive"))
      (node (ref "T39") (pin "1") (pinfunction "C_1") (pintype "passive"))
    )
    (net (code "81") (name "Net-(T40-B)") (class "Default")
      (node (ref "R41") (pin "2") (pinfunction "2_2") (pintype "passive"))
      (node (ref "T40") (pin "2") (pinfunction "B_2") (pintype "passive"))
    )
    (net (code "82") (name "Net-(T40-C)") (class "Default")
      (node (ref "JP4") (pin "11") (pinfunction "11_11") (pintype "passive"))
      (node (ref "T40") (pin "1") (pinfunction "C_1") (pintype "passive"))
    )
    (net (code "83") (name "Net-(T41-B)") (class "Default")
      (node (ref "R42") (pin "2") (pinfunction "2_2") (pintype "passive"))
      (node (ref "T41") (pin "2") (pinfunction "B_2") (pintype "passive"))
    )
    (net (code "84") (name "Net-(T41-C)") (class "Default")
      (node (ref "JP4") (pin "9") (pinfunction "9_9") (pintype "passive"))
      (node (ref "T41") (pin "1") (pinfunction "C_1") (pintype "passive"))
    )
    (net (code "85") (name "Net-(T42-B)") (class "Default")
      (node (ref "R43") (pin "2") (pinfunction "2_2") (pintype "passive"))
      (node (ref "T42") (pin "2") (pinfunction "B_2") (pintype "passive"))
    )
    (net (code "86") (name "Net-(T42-C)") (class "Default")
      (node (ref "JP4") (pin "8") (pinfunction "8_8") (pintype "passive"))
      (node (ref "T42") (pin "1") (pinfunction "C_1") (pintype "passive"))
    )
    (net (code "87") (name "Net-(T43-B)") (class "Default")
      (node (ref "R44") (pin "2") (pinfunction "2_2") (pintype "passive"))
      (node (ref "T43") (pin "2") (pinfunction "B_2") (pintype "passive"))
    )
    (net (code "88") (name "Net-(T43-C)") (class "Default")
      (node (ref "JP4") (pin "5") (pinfunction "5_5") (pintype "passive"))
      (node (ref "T43") (pin "1") (pinfunction "C_1") (pintype "passive"))
    )
    (net (code "89") (name "Net-(T44-B)") (class "Default")
      (node (ref "R45") (pin "2") (pinfunction "2_2") (pintype "passive"))
      (node (ref "T44") (pin "2") (pinfunction "B_2") (pintype "passive"))
    )
    (net (code "90") (name "Net-(T44-C)") (class "Default")
      (node (ref "JP4") (pin "3") (pinfunction "3_3") (pintype "passive"))
      (node (ref "T44") (pin "1") (pinfunction "C_1") (pintype "passive"))
    )
    (net (code "91") (name "Net-(T45-B)") (class "Default")
      (node (ref "R46") (pin "2") (pinfunction "2_2") (pintype "passive"))
      (node (ref "T45") (pin "2") (pinfunction "B_2") (pintype "passive"))
    )
    (net (code "92") (name "Net-(T45-C)") (class "Default")
      (node (ref "JP4") (pin "1") (pinfunction "1_1") (pintype "passive"))
      (node (ref "T45") (pin "1") (pinfunction "C_1") (pintype "passive"))
    )
    (net (code "93") (name "Net-(T46-B)") (class "Default")
      (node (ref "R47") (pin "2") (pinfunction "2_2") (pintype "passive"))
      (node (ref "T46") (pin "2") (pinfunction "B_2") (pintype "passive"))
    )
    (net (code "94") (name "Net-(T46-C)") (class "Default")
      (node (ref "JP4") (pin "2") (pinfunction "2_2") (pintype "passive"))
      (node (ref "T46") (pin "1") (pinfunction "C_1") (pintype "passive"))
    )
    (net (code "95") (name "Net-(T47-B)") (class "Default")
      (node (ref "R48") (pin "2") (pinfunction "2_2") (pintype "passive"))
      (node (ref "T47") (pin "2") (pinfunction "B_2") (pintype "passive"))
    )
    (net (code "96") (name "Net-(T47-C)") (class "Default")
      (node (ref "JP4") (pin "4") (pinfunction "4_4") (pintype "passive"))
      (node (ref "T47") (pin "1") (pinfunction "C_1") (pintype "passive"))
    )
    (net (code "97") (name "Net-(T48-B)") (class "Default")
      (node (ref "R49") (pin "2") (pinfunction "2_2") (pintype "passive"))
      (node (ref "T48") (pin "2") (pinfunction "B_2") (pintype "passive"))
    )
    (net (code "98") (name "Net-(T48-C)") (class "Default")
      (node (ref "JP4") (pin "6") (pinfunction "6_6") (pintype "passive"))
      (node (ref "T48") (pin "1") (pinfunction "C_1") (pintype "passive"))
    )
    (net (code "99") (name "Net-(T49-B)") (class "Default")
      (node (ref "R50") (pin "2") (pinfunction "2_2") (pintype "passive"))
      (node (ref "T49") (pin "2") (pinfunction "B_2") (pintype "passive"))
    )
    (net (code "100") (name "Net-(T49-C)") (class "Default")
      (node (ref "JP5") (pin "10") (pinfunction "10_10") (pintype "passive"))
      (node (ref "T49") (pin "1") (pinfunction "C_1") (pintype "passive"))
    )
    (net (code "101") (name "Net-(T50-B)") (class "Default")
      (node (ref "R51") (pin "2") (pinfunction "2_2") (pintype "passive"))
      (node (ref "T50") (pin "2") (pinfunction "B_2") (pintype "passive"))
    )
    (net (code "102") (name "Net-(T50-C)") (class "Default")
      (node (ref "JP5") (pin "12") (pinfunction "12_12") (pintype "passive"))
      (node (ref "T50") (pin "1") (pinfunction "C_1") (pintype "passive"))
    )
    (net (code "103") (name "Net-(T51-B)") (class "Default")
      (node (ref "R52") (pin "2") (pinfunction "2_2") (pintype "passive"))
      (node (ref "T51") (pin "2") (pinfunction "B_2") (pintype "passive"))
    )
    (net (code "104") (name "Net-(T51-C)") (class "Default")
      (node (ref "JP5") (pin "14") (pinfunction "14_14") (pintype "passive"))
      (node (ref "T51") (pin "1") (pinfunction "C_1") (pintype "passive"))
    )
    (net (code "105") (name "Net-(T52-B)") (class "Default")
      (node (ref "R53") (pin "2") (pinfunction "2_2") (pintype "passive"))
      (node (ref "T52") (pin "2") (pinfunction "B_2") (pintype "passive"))
    )
    (net (code "106") (name "Net-(T52-C)") (class "Default")
      (node (ref "JP5") (pin "11") (pinfunction "11_11") (pintype "passive"))
      (node (ref "T52") (pin "1") (pinfunction "C_1") (pintype "passive"))
    )
    (net (code "107") (name "Net-(T53-B)") (class "Default")
      (node (ref "R54") (pin "2") (pinfunction "2_2") (pintype "passive"))
      (node (ref "T53") (pin "2") (pinfunction "B_2") (pintype "passive"))
    )
    (net (code "108") (name "Net-(T53-C)") (class "Default")
      (node (ref "JP5") (pin "9") (pinfunction "9_9") (pintype "passive"))
      (node (ref "T53") (pin "1") (pinfunction "C_1") (pintype "passive"))
    )
    (net (code "109") (name "Net-(T54-B)") (class "Default")
      (node (ref "R55") (pin "2") (pinfunction "2_2") (pintype "passive"))
      (node (ref "T54") (pin "2") (pinfunction "B_2") (pintype "passive"))
    )
    (net (code "110") (name "Net-(T54-C)") (class "Default")
      (node (ref "JP5") (pin "8") (pinfunction "8_8") (pintype "passive"))
      (node (ref "T54") (pin "1") (pinfunction "C_1") (pintype "passive"))
    )
    (net (code "111") (name "Net-(T55-B)") (class "Default")
      (node (ref "R56") (pin "2") (pinfunction "2_2") (pintype "passive"))
      (node (ref "T55") (pin "2") (pinfunction "B_2") (pintype "passive"))
    )
    (net (code "112") (name "Net-(T55-C)") (class "Default")
      (node (ref "JP5") (pin "5") (pinfunction "5_5") (pintype "passive"))
      (node (ref "T55") (pin "1") (pinfunction "C_1") (pintype "passive"))
    )
    (net (code "113") (name "Net-(T56-B)") (class "Default")
      (node (ref "R57") (pin "2") (pinfunction "2_2") (pintype "passive"))
      (node (ref "T56") (pin "2") (pinfunction "B_2") (pintype "passive"))
    )
    (net (code "114") (name "Net-(T56-C)") (class "Default")
      (node (ref "JP5") (pin "3") (pinfunction "3_3") (pintype "passive"))
      (node (ref "T56") (pin "1") (pinfunction "C_1") (pintype "passive"))
    )
    (net (code "115") (name "Net-(T57-B)") (class "Default")
      (node (ref "R58") (pin "2") (pinfunction "2_2") (pintype "passive"))
      (node (ref "T57") (pin "2") (pinfunction "B_2") (pintype "passive"))
    )
    (net (code "116") (name "Net-(T57-C)") (class "Default")
      (node (ref "JP5") (pin "1") (pinfunction "1_1") (pintype "passive"))
      (node (ref "T57") (pin "1") (pinfunction "C_1") (pintype "passive"))
    )
    (net (code "117") (name "Net-(T58-B)") (class "Default")
      (node (ref "R59") (pin "2") (pinfunction "2_2") (pintype "passive"))
      (node (ref "T58") (pin "2") (pinfunction "B_2") (pintype "passive"))
    )
    (net (code "118") (name "Net-(T58-C)") (class "Default")
      (node (ref "JP5") (pin "2") (pinfunction "2_2") (pintype "passive"))
      (node (ref "T58") (pin "1") (pinfunction "C_1") (pintype "passive"))
    )
    (net (code "119") (name "Net-(T59-B)") (class "Default")
      (node (ref "R60") (pin "2") (pinfunction "2_2") (pintype "passive"))
      (node (ref "T59") (pin "2") (pinfunction "B_2") (pintype "passive"))
    )
    (net (code "120") (name "Net-(T59-C)") (class "Default")
      (node (ref "JP5") (pin "4") (pinfunction "4_4") (pintype "passive"))
      (node (ref "T59") (pin "1") (pinfunction "C_1") (pintype "passive"))
    )
    (net (code "121") (name "Net-(T60-B)") (class "Default")
      (node (ref "R61") (pin "2") (pinfunction "2_2") (pintype "passive"))
      (node (ref "T60") (pin "2") (pinfunction "B_2") (pintype "passive"))
    )
    (net (code "122") (name "Net-(T60-C)") (class "Default")
      (node (ref "JP5") (pin "6") (pinfunction "6_6") (pintype "passive"))
      (node (ref "T60") (pin "1") (pinfunction "C_1") (pintype "passive"))
    )
    (net (code "123") (name "Net-(T61-B)") (class "Default")
      (node (ref "R62") (pin "2") (pinfunction "2_2") (pintype "passive"))
      (node (ref "T61") (pin "2") (pinfunction "B_2") (pintype "passive"))
    )
    (net (code "124") (name "Net-(T61-C)") (class "Default")
      (node (ref "JP6") (pin "10") (pinfunction "10_10") (pintype "passive"))
      (node (ref "T61") (pin "1") (pinfunction "C_1") (pintype "passive"))
    )
    (net (code "125") (name "Net-(T62-B)") (class "Default")
      (node (ref "R63") (pin "2") (pinfunction "2_2") (pintype "passive"))
      (node (ref "T62") (pin "2") (pinfunction "B_2") (pintype "passive"))
    )
    (net (code "126") (name "Net-(T62-C)") (class "Default")
      (node (ref "JP6") (pin "12") (pinfunction "12_12") (pintype "passive"))
      (node (ref "T62") (pin "1") (pinfunction "C_1") (pintype "passive"))
    )
    (net (code "127") (name "Net-(T63-B)") (class "Default")
      (node (ref "R64") (pin "2") (pinfunction "2_2") (pintype "passive"))
      (node (ref "T63") (pin "2") (pinfunction "B_2") (pintype "passive"))
    )
    (net (code "128") (name "Net-(T63-C)") (class "Default")
      (node (ref "JP6") (pin "14") (pinfunction "14_14") (pintype "passive"))
      (node (ref "T63") (pin "1") (pinfunction "C_1") (pintype "passive"))
    )
    (net (code "129") (name "Net-(T64-B)") (class "Default")
      (node (ref "R65") (pin "2") (pinfunction "2_2") (pintype "passive"))
      (node (ref "T64") (pin "2") (pinfunction "B_2") (pintype "passive"))
    )
    (net (code "130") (name "Net-(T64-C)") (class "Default")
      (node (ref "JP6") (pin "11") (pinfunction "11_11") (pintype "passive"))
      (node (ref "T64") (pin "1") (pinfunction "C_1") (pintype "passive"))
    )
    (net (code "131") (name "Net-(T65-B)") (class "Default")
      (node (ref "R66") (pin "2") (pinfunction "2_2") (pintype "passive"))
      (node (ref "T65") (pin "2") (pinfunction "B_2") (pintype "passive"))
    )
    (net (code "132") (name "Net-(T65-C)") (class "Default")
      (node (ref "JP6") (pin "9") (pinfunction "9_9") (pintype "passive"))
      (node (ref "T65") (pin "1") (pinfunction "C_1") (pintype "passive"))
    )
    (net (code "133") (name "Net-(T66-B)") (class "Default")
      (node (ref "R67") (pin "2") (pinfunction "2_2") (pintype "passive"))
      (node (ref "T66") (pin "2") (pinfunction "B_2") (pintype "passive"))
    )
    (net (code "134") (name "Net-(T66-C)") (class "Default")
      (node (ref "JP6") (pin "8") (pinfunction "8_8") (pintype "passive"))
      (node (ref "T66") (pin "1") (pinfunction "C_1") (pintype "passive"))
    )
    (net (code "135") (name "Net-(T67-B)") (class "Default")
      (node (ref "R68") (pin "2") (pinfunction "2_2") (pintype "passive"))
      (node (ref "T67") (pin "2") (pinfunction "B_2") (pintype "passive"))
    )
    (net (code "136") (name "Net-(T67-C)") (class "Default")
      (node (ref "JP6") (pin "5") (pinfunction "5_5") (pintype "passive"))
      (node (ref "T67") (pin "1") (pinfunction "C_1") (pintype "passive"))
    )
    (net (code "137") (name "Net-(T68-B)") (class "Default")
      (node (ref "R69") (pin "2") (pinfunction "2_2") (pintype "passive"))
      (node (ref "T68") (pin "2") (pinfunction "B_2") (pintype "passive"))
    )
    (net (code "138") (name "Net-(T68-C)") (class "Default")
      (node (ref "JP6") (pin "3") (pinfunction "3_3") (pintype "passive"))
      (node (ref "T68") (pin "1") (pinfunction "C_1") (pintype "passive"))
    )
    (net (code "139") (name "Net-(T69-B)") (class "Default")
      (node (ref "R70") (pin "2") (pinfunction "2_2") (pintype "passive"))
      (node (ref "T69") (pin "2") (pinfunction "B_2") (pintype "passive"))
    )
    (net (code "140") (name "Net-(T69-C)") (class "Default")
      (node (ref "JP6") (pin "1") (pinfunction "1_1") (pintype "passive"))
      (node (ref "T69") (pin "1") (pinfunction "C_1") (pintype "passive"))
    )
    (net (code "141") (name "Net-(T70-B)") (class "Default")
      (node (ref "R71") (pin "2") (pinfunction "2_2") (pintype "passive"))
      (node (ref "T70") (pin "2") (pinfunction "B_2") (pintype "passive"))
    )
    (net (code "142") (name "Net-(T70-C)") (class "Default")
      (node (ref "JP6") (pin "2") (pinfunction "2_2") (pintype "passive"))
      (node (ref "T70") (pin "1") (pinfunction "C_1") (pintype "passive"))
    )
    (net (code "143") (name "Net-(T71-B)") (class "Default")
      (node (ref "R72") (pin "2") (pinfunction "2_2") (pintype "passive"))
      (node (ref "T71") (pin "2") (pinfunction "B_2") (pintype "passive"))
    )
    (net (code "144") (name "Net-(T71-C)") (class "Default")
      (node (ref "JP6") (pin "4") (pinfunction "4_4") (pintype "passive"))
      (node (ref "T71") (pin "1") (pinfunction "C_1") (pintype "passive"))
    )
    (net (code "145") (name "Net-(T72-B)") (class "Default")
      (node (ref "R73") (pin "2") (pinfunction "2_2") (pintype "passive"))
      (node (ref "T72") (pin "2") (pinfunction "B_2") (pintype "passive"))
    )
    (net (code "146") (name "Net-(T72-C)") (class "Default")
      (node (ref "JP6") (pin "6") (pinfunction "6_6") (pintype "passive"))
      (node (ref "T72") (pin "1") (pinfunction "C_1") (pintype "passive"))
    )
    (net (code "147") (name "unconnected-(J1B-S-Pad2)") (class "Default")
      (node (ref "J1") (pin "2") (pinfunction "S_2") (pintype "passive"))
    )
    (net (code "148") (name "unconnected-(JP1-Pad7)") (class "Default")
      (node (ref "JP1") (pin "7") (pinfunction "7_7") (pintype "passive"))
    )
    (net (code "149") (name "unconnected-(JP1-Pad13)") (class "Default")
      (node (ref "JP1") (pin "13") (pinfunction "13_13") (pintype "passive"))
    )
    (net (code "150") (name "unconnected-(JP2-Pad7)") (class "Default")
      (node (ref "JP2") (pin "7") (pinfunction "7_7") (pintype "passive"))
    )
    (net (code "151") (name "unconnected-(JP2-Pad13)") (class "Default")
      (node (ref "JP2") (pin "13") (pinfunction "13_13") (pintype "passive"))
    )
    (net (code "152") (name "unconnected-(JP3-Pad7)") (class "Default")
      (node (ref "JP3") (pin "7") (pinfunction "7_7") (pintype "passive"))
    )
    (net (code "153") (name "unconnected-(JP3-Pad13)") (class "Default")
      (node (ref "JP3") (pin "13") (pinfunction "13_13") (pintype "passive"))
    )
    (net (code "154") (name "unconnected-(JP4-Pad7)") (class "Default")
      (node (ref "JP4") (pin "7") (pinfunction "7_7") (pintype "passive"))
    )
    (net (code "155") (name "unconnected-(JP4-Pad13)") (class "Default")
      (node (ref "JP4") (pin "13") (pinfunction "13_13") (pintype "passive"))
    )
    (net (code "156") (name "unconnected-(JP5-Pad7)") (class "Default")
      (node (ref "JP5") (pin "7") (pinfunction "7_7") (pintype "passive"))
    )
    (net (code "157") (name "unconnected-(JP5-Pad13)") (class "Default")
      (node (ref "JP5") (pin "13") (pinfunction "13_13") (pintype "passive"))
    )
    (net (code "158") (name "unconnected-(JP6-Pad7)") (class "Default")
      (node (ref "JP6") (pin "7") (pinfunction "7_7") (pintype "passive"))
    )
    (net (code "159") (name "unconnected-(JP6-Pad13)") (class "Default")
      (node (ref "JP6") (pin "13") (pinfunction "13_13") (pintype "passive"))
    )
    (net (code "160") (name "unconnected-(R1-Pad1)") (class "Default")
      (node (ref "R1") (pin "1") (pinfunction "1_1") (pintype "passive"))
    )
    (net (code "161") (name "unconnected-(R2-Pad1)") (class "Default")
      (node (ref "R2") (pin "1") (pinfunction "1_1") (pintype "passive"))
    )
    (net (code "162") (name "unconnected-(R3-Pad1)") (class "Default")
      (node (ref "R3") (pin "1") (pinfunction "1_1") (pintype "passive"))
    )
    (net (code "163") (name "unconnected-(R4-Pad1)") (class "Default")
      (node (ref "R4") (pin "1") (pinfunction "1_1") (pintype "passive"))
    )
    (net (code "164") (name "unconnected-(R5-Pad1)") (class "Default")
      (node (ref "R5") (pin "1") (pinfunction "1_1") (pintype "passive"))
    )
    (net (code "165") (name "unconnected-(R6-Pad1)") (class "Default")
      (node (ref "R6") (pin "1") (pinfunction "1_1") (pintype "passive"))
    )
    (net (code "166") (name "unconnected-(R7-Pad1)") (class "Default")
      (node (ref "R7") (pin "1") (pinfunction "1_1") (pintype "passive"))
    )
    (net (code "167") (name "unconnected-(R8-Pad1)") (class "Default")
      (node (ref "R8") (pin "1") (pinfunction "1_1") (pintype "passive"))
    )
    (net (code "168") (name "unconnected-(R9-Pad1)") (class "Default")
      (node (ref "R9") (pin "1") (pinfunction "1_1") (pintype "passive"))
    )
    (net (code "169") (name "unconnected-(R10-Pad1)") (class "Default")
      (node (ref "R10") (pin "1") (pinfunction "1_1") (pintype "passive"))
    )
    (net (code "170") (name "unconnected-(R11-Pad1)") (class "Default")
      (node (ref "R11") (pin "1") (pinfunction "1_1") (pintype "passive"))
    )
    (net (code "171") (name "unconnected-(R12-Pad1)") (class "Default")
      (node (ref "R12") (pin "1") (pinfunction "1_1") (pintype "passive"))
    )
    (net (code "172") (name "unconnected-(R13-Pad2)") (class "Default")
      (node (ref "R13") (pin "2") (pinfunction "2_2") (pintype "passive"))
    )
    (net (code "173") (name "unconnected-(R14-Pad1)") (class "Default")
      (node (ref "R14") (pin "1") (pinfunction "1_1") (pintype "passive"))
    )
    (net (code "174") (name "unconnected-(R15-Pad1)") (class "Default")
      (node (ref "R15") (pin "1") (pinfunction "1_1") (pintype "passive"))
    )
    (net (code "175") (name "unconnected-(R16-Pad1)") (class "Default")
      (node (ref "R16") (pin "1") (pinfunction "1_1") (pintype "passive"))
    )
    (net (code "176") (name "unconnected-(R17-Pad1)") (class "Default")
      (node (ref "R17") (pin "1") (pinfunction "1_1") (pintype "passive"))
    )
    (net (code "177") (name "unconnected-(R18-Pad1)") (class "Default")
      (node (ref "R18") (pin "1") (pinfunction "1_1") (pintype "passive"))
    )
    (net (code "178") (name "unconnected-(R19-Pad1)") (class "Default")
      (node (ref "R19") (pin "1") (pinfunction "1_1") (pintype "passive"))
    )
    (net (code "179") (name "unconnected-(R20-Pad1)") (class "Default")
      (node (ref "R20") (pin "1") (pinfunction "1_1") (pintype "passive"))
    )
    (net (code "180") (name "unconnected-(R21-Pad1)") (class "Default")
      (node (ref "R21") (pin "1") (pinfunction "1_1") (pintype "passive"))
    )
    (net (code "181") (name "unconnected-(R22-Pad1)") (class "Default")
      (node (ref "R22") (pin "1") (pinfunction "1_1") (pintype "passive"))
    )
    (net (code "182") (name "unconnected-(R23-Pad1)") (class "Default")
      (node (ref "R23") (pin "1") (pinfunction "1_1") (pintype "passive"))
    )
    (net (code "183") (name "unconnected-(R24-Pad1)") (class "Default")
      (node (ref "R24") (pin "1") (pinfunction "1_1") (pintype "passive"))
    )
    (net (code "184") (name "unconnected-(R25-Pad1)") (class "Default")
      (node (ref "R25") (pin "1") (pinfunction "1_1") (pintype "passive"))
    )
    (net (code "185") (name "unconnected-(R26-Pad1)") (class "Default")
      (node (ref "R26") (pin "1") (pinfunction "1_1") (pintype "passive"))
    )
    (net (code "186") (name "unconnected-(R27-Pad1)") (class "Default")
      (node (ref "R27") (pin "1") (pinfunction "1_1") (pintype "passive"))
    )
    (net (code "187") (name "unconnected-(R28-Pad1)") (class "Default")
      (node (ref "R28") (pin "1") (pinfunction "1_1") (pintype "passive"))
    )
    (net (code "188") (name "unconnected-(R29-Pad1)") (class "Default")
      (node (ref "R29") (pin "1") (pinfunction "1_1") (pintype "passive"))
    )
    (net (code "189") (name "unconnected-(R30-Pad1)") (class "Default")
      (node (ref "R30") (pin "1") (pinfunction "1_1") (pintype "passive"))
    )
    (net (code "190") (name "unconnected-(R31-Pad1)") (class "Default")
      (node (ref "R31") (pin "1") (pinfunction "1_1") (pintype "passive"))
    )
    (net (code "191") (name "unconnected-(R32-Pad1)") (class "Default")
      (node (ref "R32") (pin "1") (pinfunction "1_1") (pintype "passive"))
    )
    (net (code "192") (name "unconnected-(R33-Pad1)") (class "Default")
      (node (ref "R33") (pin "1") (pinfunction "1_1") (pintype "passive"))
    )
    (net (code "193") (name "unconnected-(R34-Pad1)") (class "Default")
      (node (ref "R34") (pin "1") (pinfunction "1_1") (pintype "passive"))
    )
    (net (code "194") (name "unconnected-(R35-Pad1)") (class "Default")
      (node (ref "R35") (pin "1") (pinfunction "1_1") (pintype "passive"))
    )
    (net (code "195") (name "unconnected-(R36-Pad1)") (class "Default")
      (node (ref "R36") (pin "1") (pinfunction "1_1") (pintype "passive"))
    )
    (net (code "196") (name "unconnected-(R37-Pad1)") (class "Default")
      (node (ref "R37") (pin "1") (pinfunction "1_1") (pintype "passive"))
    )
    (net (code "197") (name "unconnected-(R38-Pad1)") (class "Default")
      (node (ref "R38") (pin "1") (pinfunction "1_1") (pintype "passive"))
    )
    (net (code "198") (name "unconnected-(R39-Pad1)") (class "Default")
      (node (ref "R39") (pin "1") (pinfunction "1_1") (pintype "passive"))
    )
    (net (code "199") (name "unconnected-(R40-Pad1)") (class "Default")
      (node (ref "R40") (pin "1") (pinfunction "1_1") (pintype "passive"))
    )
    (net (code "200") (name "unconnected-(R41-Pad1)") (class "Default")
      (node (ref "R41") (pin "1") (pinfunction "1_1") (pintype "passive"))
    )
    (net (code "201") (name "unconnected-(R42-Pad1)") (class "Default")
      (node (ref "R42") (pin "1") (pinfunction "1_1") (pintype "passive"))
    )
    (net (code "202") (name "unconnected-(R43-Pad1)") (class "Default")
      (node (ref "R43") (pin "1") (pinfunction "1_1") (pintype "passive"))
    )
    (net (code "203") (name "unconnected-(R44-Pad1)") (class "Default")
      (node (ref "R44") (pin "1") (pinfunction "1_1") (pintype "passive"))
    )
    (net (code "204") (name "unconnected-(R45-Pad1)") (class "Default")
      (node (ref "R45") (pin "1") (pinfunction "1_1") (pintype "passive"))
    )
    (net (code "205") (name "unconnected-(R46-Pad1)") (class "Default")
      (node (ref "R46") (pin "1") (pinfunction "1_1") (pintype "passive"))
    )
    (net (code "206") (name "unconnected-(R47-Pad1)") (class "Default")
      (node (ref "R47") (pin "1") (pinfunction "1_1") (pintype "passive"))
    )
    (net (code "207") (name "unconnected-(R48-Pad1)") (class "Default")
      (node (ref "R48") (pin "1") (pinfunction "1_1") (pintype "passive"))
    )
    (net (code "208") (name "unconnected-(R49-Pad1)") (class "Default")
      (node (ref "R49") (pin "1") (pinfunction "1_1") (pintype "passive"))
    )
    (net (code "209") (name "unconnected-(R50-Pad1)") (class "Default")
      (node (ref "R50") (pin "1") (pinfunction "1_1") (pintype "passive"))
    )
    (net (code "210") (name "unconnected-(R51-Pad1)") (class "Default")
      (node (ref "R51") (pin "1") (pinfunction "1_1") (pintype "passive"))
    )
    (net (code "211") (name "unconnected-(R52-Pad1)") (class "Default")
      (node (ref "R52") (pin "1") (pinfunction "1_1") (pintype "passive"))
    )
    (net (code "212") (name "unconnected-(R53-Pad1)") (class "Default")
      (node (ref "R53") (pin "1") (pinfunction "1_1") (pintype "passive"))
    )
    (net (code "213") (name "unconnected-(R54-Pad1)") (class "Default")
      (node (ref "R54") (pin "1") (pinfunction "1_1") (pintype "passive"))
    )
    (net (code "214") (name "unconnected-(R55-Pad1)") (class "Default")
      (node (ref "R55") (pin "1") (pinfunction "1_1") (pintype "passive"))
    )
    (net (code "215") (name "unconnected-(R56-Pad1)") (class "Default")
      (node (ref "R56") (pin "1") (pinfunction "1_1") (pintype "passive"))
    )
    (net (code "216") (name "unconnected-(R57-Pad1)") (class "Default")
      (node (ref "R57") (pin "1") (pinfunction "1_1") (pintype "passive"))
    )
    (net (code "217") (name "unconnected-(R58-Pad1)") (class "Default")
      (node (ref "R58") (pin "1") (pinfunction "1_1") (pintype "passive"))
    )
    (net (code "218") (name "unconnected-(R59-Pad1)") (class "Default")
      (node (ref "R59") (pin "1") (pinfunction "1_1") (pintype "passive"))
    )
    (net (code "219") (name "unconnected-(R60-Pad1)") (class "Default")
      (node (ref "R60") (pin "1") (pinfunction "1_1") (pintype "passive"))
    )
    (net (code "220") (name "unconnected-(R61-Pad1)") (class "Default")
      (node (ref "R61") (pin "1") (pinfunction "1_1") (pintype "passive"))
    )
    (net (code "221") (name "unconnected-(R62-Pad1)") (class "Default")
      (node (ref "R62") (pin "1") (pinfunction "1_1") (pintype "passive"))
    )
    (net (code "222") (name "unconnected-(R63-Pad1)") (class "Default")
      (node (ref "R63") (pin "1") (pinfunction "1_1") (pintype "passive"))
    )
    (net (code "223") (name "unconnected-(R64-Pad1)") (class "Default")
      (node (ref "R64") (pin "1") (pinfunction "1_1") (pintype "passive"))
    )
    (net (code "224") (name "unconnected-(R65-Pad1)") (class "Default")
      (node (ref "R65") (pin "1") (pinfunction "1_1") (pintype "passive"))
    )
    (net (code "225") (name "unconnected-(R66-Pad1)") (class "Default")
      (node (ref "R66") (pin "1") (pinfunction "1_1") (pintype "passive"))
    )
    (net (code "226") (name "unconnected-(R67-Pad1)") (class "Default")
      (node (ref "R67") (pin "1") (pinfunction "1_1") (pintype "passive"))
    )
    (net (code "227") (name "unconnected-(R68-Pad1)") (class "Default")
      (node (ref "R68") (pin "1") (pinfunction "1_1") (pintype "passive"))
    )
    (net (code "228") (name "unconnected-(R69-Pad1)") (class "Default")
      (node (ref "R69") (pin "1") (pinfunction "1_1") (pintype "passive"))
    )
    (net (code "229") (name "unconnected-(R70-Pad1)") (class "Default")
      (node (ref "R70") (pin "1") (pinfunction "1_1") (pintype "passive"))
    )
    (net (code "230") (name "unconnected-(R71-Pad1)") (class "Default")
      (node (ref "R71") (pin "1") (pinfunction "1_1") (pintype "passive"))
    )
    (net (code "231") (name "unconnected-(R72-Pad1)") (class "Default")
      (node (ref "R72") (pin "1") (pinfunction "1_1") (pintype "passive"))
    )
    (net (code "232") (name "unconnected-(R73-Pad1)") (class "Default")
      (node (ref "R73") (pin "1") (pinfunction "1_1") (pintype "passive"))
    )
  )
)
